# Regulators.net
KiCad netlist of a schematic drawn in Altium Designer
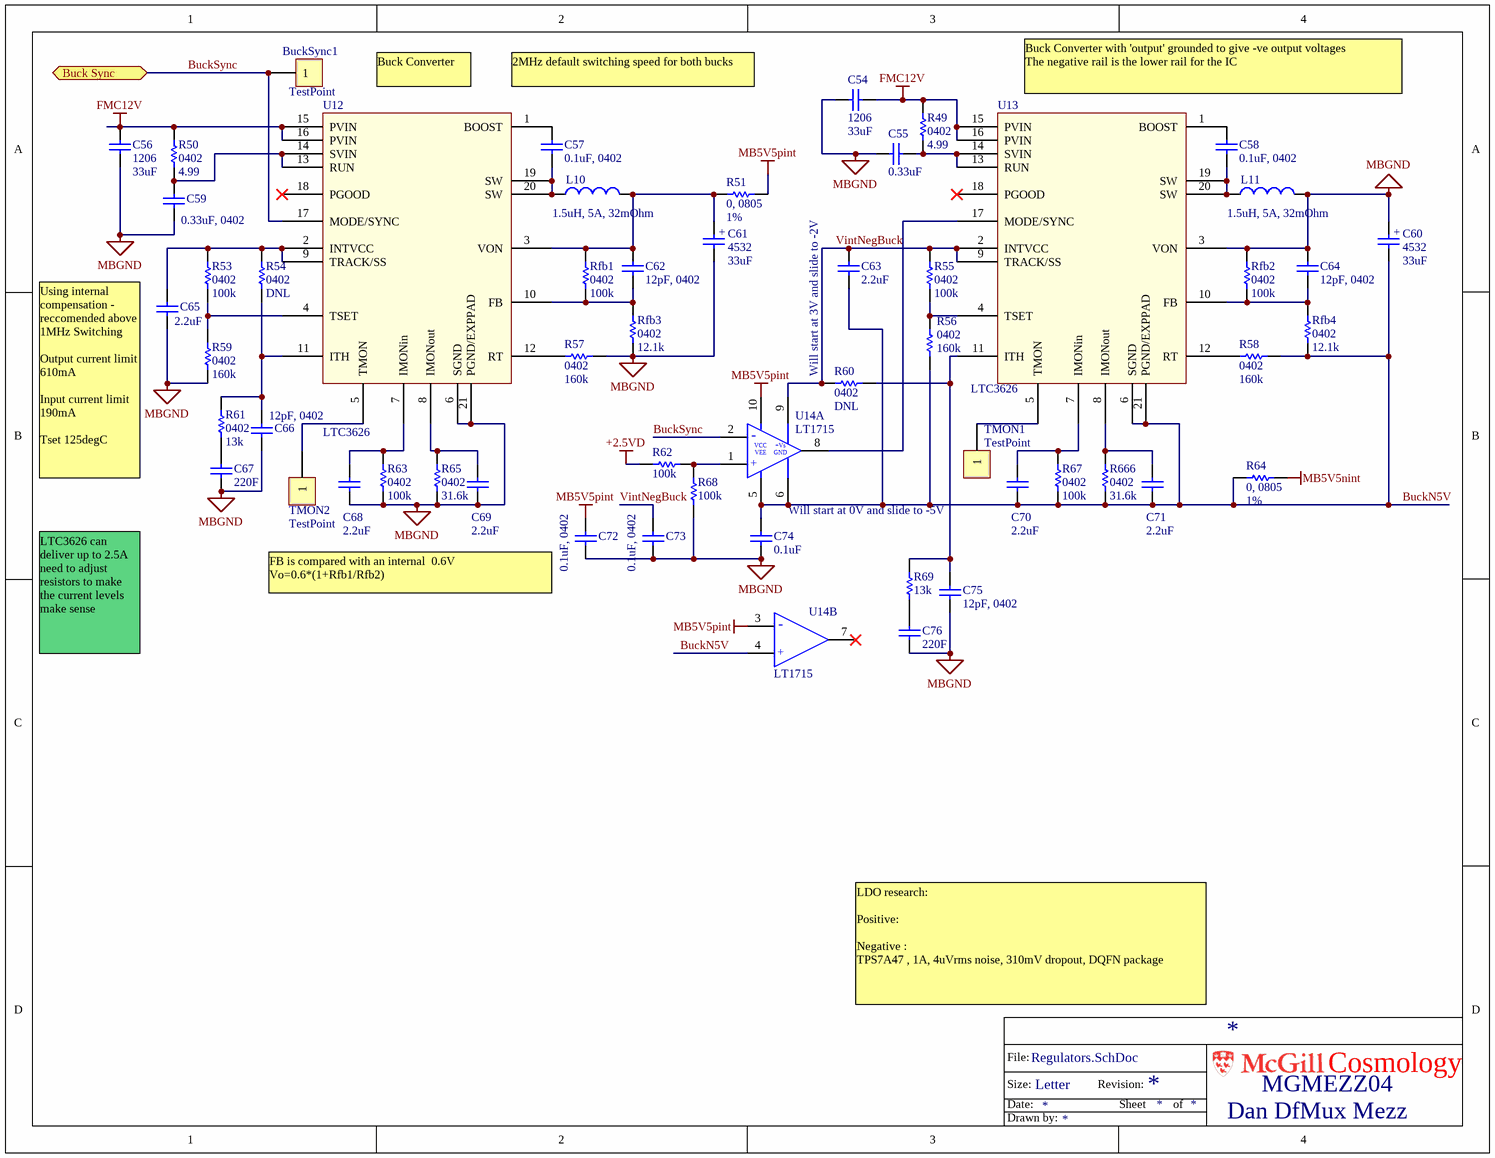
[diagram p0: Regulators.SchDoc]

(export (version "E")
  (design (tool "Eeschema 10.0.6"))
  (components
    (comp (ref "BuckSync1")
      (value "TestPoint")
      (footprint "TP-3520-SK")
      (description "TestPoint1")
      (libsource (lib "") (part "TestPoint_1"))
    )
    (comp (ref "C54")
      (value "33uF")
      (footprint "1206")
      (description "Capacitor, Ceramic, 1210")
      (fields
        (field (name "MANUFACTURER") "TDK Corporation")
        (field (name "MANUFACTURERS PART NUMBER") "C3216X5R1E336M")
      )
      (libsource (lib "MGMEZZ04") (part "CAP 1210"))
    )
    (comp (ref "C55")
      (value "0.33uF")
      (footprint "0603")
      (description "Capacitor, Ceramic, 0603")
      (fields (field (name "MANUFACTURER") "Generic"))
      (libsource (lib "MGMEZZ04") (part "CAP 0603"))
    )
    (comp (ref "C56")
      (value "33uF")
      (footprint "1206")
      (description "Capacitor, Ceramic, 1210")
      (fields
        (field (name "MANUFACTURER") "TDK Corporation")
        (field (name "MANUFACTURERS PART NUMBER") "C3216X5R1E336M")
      )
      (libsource (lib "MGMEZZ04") (part "CAP 1210"))
    )
    (comp (ref "C57")
      (value "0.1uF, 0402")
      (footprint "0402")
      (description "Capacitor, Ceramic, 0402")
      (fields (field (name "MANUFACTURER") "Generic") (field (name "TOLERANCE") "±10%"))
      (libsource (lib "MGMEZZ04") (part "CAP 0603"))
    )
    (comp (ref "C58")
      (value "0.1uF, 0402")
      (footprint "0402")
      (description "Capacitor, Ceramic, 0402")
      (fields (field (name "MANUFACTURER") "Generic") (field (name "TOLERANCE") "±10%"))
      (libsource (lib "MGMEZZ04") (part "CAP 0603"))
    )
    (comp (ref "C59")
      (value "0.33uF, 0402")
      (footprint "0402")
      (description "Capacitor, Ceramic, 0402")
      (fields (field (name "MANUFACTURER") "Generic") (field (name "TOLERANCE") "±10%"))
      (libsource (lib "MGMEZZ04") (part "CAP 0603"))
    )
    (comp (ref "C60")
      (value "33uF")
      (footprint "4532")
      (description "33u, 16V, 20%, 4532C, X5R")
      (fields
        (field (name "MANUFACTURER") "TDK Corporation")
        (field (name "MANUFACTURERS PART NUMBER") "C4532X5R1C336M")
      )
      (libsource (lib "MGMEZZ04") (part "CAP4532"))
    )
    (comp (ref "C61")
      (value "33uF")
      (footprint "4532")
      (description "33u, 16V, 20%, 4532C, X5R")
      (fields
        (field (name "MANUFACTURER") "TDK Corporation")
        (field (name "MANUFACTURERS PART NUMBER") "C4532X5R1C336M")
      )
      (libsource (lib "MGMEZZ04") (part "CAP4532"))
    )
    (comp (ref "C62")
      (value "12pF, 0402")
      (footprint "0402")
      (description "Capacitor, Ceramic, 0603")
      (fields (field (name "MANUFACTURER") "Generic"))
      (libsource (lib "MGMEZZ04") (part "CAP 0402"))
    )
    (comp (ref "C63")
      (value "2.2uF")
      (footprint "0603")
      (description "Capacitor, Ceramic, 0603")
      (fields (field (name "MANUFACTURER") "Generic"))
      (libsource (lib "MGMEZZ04") (part "CAP 0603"))
    )
    (comp (ref "C64")
      (value "12pF, 0402")
      (footprint "0402")
      (description "Capacitor, Ceramic, 0603")
      (fields (field (name "MANUFACTURER") "Generic"))
      (libsource (lib "MGMEZZ04") (part "CAP 0402"))
    )
    (comp (ref "C65")
      (value "2.2uF")
      (footprint "0603")
      (description "Capacitor, Ceramic, 0603")
      (fields (field (name "MANUFACTURER") "Generic"))
      (libsource (lib "MGMEZZ04") (part "CAP 0603"))
    )
    (comp (ref "C66")
      (value "12pF, 0402")
      (footprint "0402")
      (description "Capacitor, Ceramic, 0603")
      (fields (field (name "MANUFACTURER") "Generic"))
      (libsource (lib "MGMEZZ04") (part "CAP 0402"))
    )
    (comp (ref "C67")
      (value "220F")
      (footprint "0603")
      (description "Capacitor, Ceramic, 0603")
      (fields (field (name "MANUFACTURER") "Generic"))
      (libsource (lib "MGMEZZ04") (part "CAP 0603"))
    )
    (comp (ref "C68")
      (value "2.2uF")
      (footprint "0603")
      (description "Capacitor, Ceramic, 0603")
      (fields (field (name "MANUFACTURER") "Generic") (field (name "TOLERANCE") "±10%"))
      (libsource (lib "MGMEZZ04") (part "CAP 0603"))
    )
    (comp (ref "C69")
      (value "2.2uF")
      (footprint "0603")
      (description "Capacitor, Ceramic, 0603")
      (fields (field (name "MANUFACTURER") "Generic") (field (name "TOLERANCE") "±10%"))
      (libsource (lib "MGMEZZ04") (part "CAP 0603"))
    )
    (comp (ref "C70")
      (value "2.2uF")
      (footprint "0603")
      (description "Capacitor, Ceramic, 0603")
      (fields (field (name "MANUFACTURER") "Generic") (field (name "TOLERANCE") "±10%"))
      (libsource (lib "MGMEZZ04") (part "CAP 0603"))
    )
    (comp (ref "C71")
      (value "2.2uF")
      (footprint "0603")
      (description "Capacitor, Ceramic, 0603")
      (fields (field (name "MANUFACTURER") "Generic") (field (name "TOLERANCE") "±10%"))
      (libsource (lib "MGMEZZ04") (part "CAP 0603"))
    )
    (comp (ref "C72")
      (value "0.1uF, 0402")
      (footprint "0402")
      (description "Capacitor, Ceramic, 0402")
      (fields (field (name "MANUFACTURER") "Generic") (field (name "TOLERANCE") "±10%"))
      (libsource (lib "MGMEZZ04") (part "CAP 0603"))
    )
    (comp (ref "C73")
      (value "0.1uF, 0402")
      (footprint "0402")
      (description "Capacitor, Ceramic, 0402")
      (fields (field (name "MANUFACTURER") "Generic") (field (name "TOLERANCE") "±10%"))
      (libsource (lib "MGMEZZ04") (part "CAP 0603"))
    )
    (comp (ref "C74")
      (value "0.1uF")
      (footprint "0603")
      (description "Capacitor, Ceramic, 0603")
      (fields (field (name "MANUFACTURER") "Generic"))
      (libsource (lib "MGMEZZ04") (part "CAP 0603"))
    )
    (comp (ref "C75")
      (value "12pF, 0402")
      (footprint "0402")
      (description "Capacitor, Ceramic, 0603")
      (fields (field (name "MANUFACTURER") "Generic"))
      (libsource (lib "MGMEZZ04") (part "CAP 0402"))
    )
    (comp (ref "C76")
      (value "220F")
      (footprint "0603")
      (description "Capacitor, Ceramic, 0603")
      (fields (field (name "MANUFACTURER") "Generic"))
      (libsource (lib "MGMEZZ04") (part "CAP 0603"))
    )
    (comp (ref "L10")
      (value "1.5uH")
      (footprint "IHLP-1212")
      (description "Inductor IHLP1212")
      (fields
        (field (name "MANUFACTURER") "Vishay Dale")
        (field (name "MANUFACTURERS PART NUMBER") "IHLP1212BZER1R5M11")
        (field (name "PART CONSTRAINTS") "1.5uH, 5A, 32mOhm")
      )
      (libsource (lib "MGMEZZ04") (part "IND IHLP1212"))
    )
    (comp (ref "L11")
      (value "1.5uH")
      (footprint "IHLP-1212")
      (description "Inductor IHLP1212")
      (fields
        (field (name "MANUFACTURER") "Vishay Dale")
        (field (name "MANUFACTURERS PART NUMBER") "IHLP1212BZER1R5M11")
        (field (name "PART CONSTRAINTS") "1.5uH, 5A, 32mOhm")
      )
      (libsource (lib "MGMEZZ04") (part "IND IHLP1212"))
    )
    (comp (ref "R49")
      (value "4.99")
      (footprint "0402")
      (description "Resistor")
      (fields (field (name "MANUFACTURER") "Generic"))
      (libsource (lib "MGMEZZ04") (part "RES 0402"))
    )
    (comp (ref "R50")
      (value "4.99")
      (footprint "0402")
      (description "Resistor")
      (fields (field (name "MANUFACTURER") "Generic"))
      (libsource (lib "MGMEZZ04") (part "RES 0402"))
    )
    (comp (ref "R51")
      (value "0, 0805")
      (footprint "0805")
      (description "RES 0.0 OHM 1/8W 0805 SMD")
      (fields (field (name "PARAM") "1%") (field (name "MANUFACTURER") "e.g Vishay/Dale"))
      (libsource (lib "AdamsParts") (part "Res1812"))
    )
    (comp (ref "R53")
      (value "100k")
      (footprint "0402")
      (description "Resistor")
      (fields (field (name "MANUFACTURER") "Generic"))
      (libsource (lib "MGMEZZ04") (part "RES 0402"))
    )
    (comp (ref "R54")
      (value "DNL")
      (footprint "0402")
      (description "Resistor")
      (fields (field (name "MANUFACTURER") "Generic"))
      (libsource (lib "MGMEZZ04") (part "RES 0402"))
    )
    (comp (ref "R55")
      (value "100k")
      (footprint "0402")
      (description "Resistor")
      (fields (field (name "MANUFACTURER") "Generic"))
      (libsource (lib "MGMEZZ04") (part "RES 0402"))
    )
    (comp (ref "R56")
      (value "160k")
      (footprint "0402")
      (description "Resistor")
      (fields (field (name "MANUFACTURER") "Generic"))
      (libsource (lib "MGMEZZ04") (part "RES 0402"))
    )
    (comp (ref "R57")
      (value "160k")
      (footprint "0402")
      (description "Resistor")
      (fields (field (name "MANUFACTURER") "Generic"))
      (libsource (lib "MGMEZZ04") (part "RES 0402"))
    )
    (comp (ref "R58")
      (value "160k")
      (footprint "0402")
      (description "Resistor")
      (fields (field (name "MANUFACTURER") "Generic"))
      (libsource (lib "MGMEZZ04") (part "RES 0402"))
    )
    (comp (ref "R59")
      (value "160k")
      (footprint "0402")
      (description "Resistor")
      (fields (field (name "MANUFACTURER") "Generic"))
      (libsource (lib "MGMEZZ04") (part "RES 0402"))
    )
    (comp (ref "R60")
      (value "DNL")
      (footprint "0402")
      (description "Resistor")
      (fields (field (name "MANUFACTURER") "Generic"))
      (libsource (lib "MGMEZZ04") (part "RES 0402"))
    )
    (comp (ref "R61")
      (value "13k")
      (footprint "0402")
      (description "Resistor")
      (fields (field (name "MANUFACTURER") "Generic"))
      (libsource (lib "MGMEZZ04") (part "RES 0402"))
    )
    (comp (ref "R62")
      (value "100k")
      (footprint "0603")
      (description "Resistor")
      (fields (field (name "MANUFACTURER") "Generic"))
      (libsource (lib "MGMEZZ04") (part "RES 0603"))
    )
    (comp (ref "R63")
      (value "100k")
      (footprint "0402")
      (description "Resistor")
      (fields (field (name "MANUFACTURER") "Generic"))
      (libsource (lib "MGMEZZ04") (part "RES 0402"))
    )
    (comp (ref "R64")
      (value "0, 0805")
      (footprint "0805")
      (description "RES 0.0 OHM 1/8W 0805 SMD")
      (fields (field (name "PARAM") "1%") (field (name "MANUFACTURER") "e.g Vishay/Dale"))
      (libsource (lib "AdamsParts") (part "Res1812"))
    )
    (comp (ref "R65")
      (value "31.6k")
      (footprint "0402")
      (description "Resistor")
      (fields (field (name "MANUFACTURER") "Generic"))
      (libsource (lib "MGMEZZ04") (part "RES 0402"))
    )
    (comp (ref "R67")
      (value "100k")
      (footprint "0402")
      (description "Resistor")
      (fields (field (name "MANUFACTURER") "Generic"))
      (libsource (lib "MGMEZZ04") (part "RES 0402"))
    )
    (comp (ref "R68")
      (value "100k")
      (footprint "0603")
      (description "Resistor")
      (fields (field (name "MANUFACTURER") "Generic"))
      (libsource (lib "MGMEZZ04") (part "RES 0603"))
    )
    (comp (ref "R69")
      (value "13k")
      (footprint "0603")
      (description "Resistor")
      (fields (field (name "MANUFACTURER") "Generic"))
      (libsource (lib "MGMEZZ04") (part "RES 0603"))
    )
    (comp (ref "R666")
      (value "31.6k")
      (footprint "0402")
      (description "Resistor")
      (fields (field (name "MANUFACTURER") "Generic"))
      (libsource (lib "MGMEZZ04") (part "RES 0402"))
    )
    (comp (ref "Rfb1")
      (value "100k")
      (footprint "0402")
      (description "Resistor")
      (fields (field (name "MANUFACTURER") "Generic"))
      (libsource (lib "MGMEZZ04") (part "RES 0402"))
    )
    (comp (ref "Rfb2")
      (value "100k")
      (footprint "0402")
      (description "Resistor")
      (fields (field (name "MANUFACTURER") "Generic"))
      (libsource (lib "MGMEZZ04") (part "RES 0402"))
    )
    (comp (ref "Rfb3")
      (value "12.1k")
      (footprint "0402")
      (description "Resistor")
      (fields (field (name "MANUFACTURER") "Generic"))
      (libsource (lib "MGMEZZ04") (part "RES 0402"))
    )
    (comp (ref "Rfb4")
      (value "12.1k")
      (footprint "0402")
      (description "Resistor")
      (fields (field (name "MANUFACTURER") "Generic"))
      (libsource (lib "MGMEZZ04") (part "RES 0402"))
    )
    (comp (ref "TMON1")
      (value "TestPoint")
      (footprint "TP-3520-SK")
      (description "TestPoint1")
      (libsource (lib "MGMEZZ04") (part "TestPoint"))
    )
    (comp (ref "TMON2")
      (value "TestPoint")
      (footprint "TP-3520-SK")
      (description "TestPoint1")
      (libsource (lib "MGMEZZ04") (part "TestPoint"))
    )
    (comp (ref "U12")
      (value "LTC3626")
      (footprint "LTC3626")
      (description "20V, 2.5A Sync buck, 3Mhz")
      (fields
        (field (name "MANUFACTURERS PART NUMBER") "LTC3626EUDC#PBF")
        (field (name "MANUFACTURER") "Linear Technology")
      )
      (libsource (lib "MGMEZZ04") (part "LTC3626"))
    )
    (comp (ref "U13")
      (value "LTC3626")
      (footprint "LTC3626")
      (description "20V, 2.5A Sync buck, 3Mhz")
      (fields
        (field (name "MANUFACTURERS PART NUMBER") "LTC3626EUDC#PBF")
        (field (name "MANUFACTURER") "Linear Technology")
      )
      (libsource (lib "MGMEZZ04") (part "LTC3626"))
    )
    (comp (ref "U14")
      (value "LT1715")
      (footprint "TSSOP50P490X110-10N")
      (description "Comparator with two supplies")
      (libsource (lib "MGMEZZ04") (part "LT1715"))
    )
  )
  (nets
    (net (code "1") (name "+2.5VD") (class "Default")
      (node (ref "R62") (pin "2") (pinfunction "2_2") (pintype "passive"))
    )
    (net (code "2") (name "/BuckN5V") (class "Default")
      (node (ref "C60") (pin "2") (pinfunction "2_2") (pintype "passive"))
      (node (ref "C63") (pin "1") (pinfunction "1_1") (pintype "passive"))
      (node (ref "C70") (pin "2") (pinfunction "2_2") (pintype "passive"))
      (node (ref "C71") (pin "2") (pinfunction "2_2") (pintype "passive"))
      (node (ref "C74") (pin "2") (pinfunction "2_2") (pintype "passive"))
      (node (ref "R56") (pin "2") (pinfunction "2_2") (pintype "passive"))
      (node (ref "R58") (pin "2") (pinfunction "2_2") (pintype "passive"))
      (node (ref "R64") (pin "2") (pinfunction "2_2") (pintype "passive"))
      (node (ref "R666") (pin "2") (pinfunction "2_2") (pintype "passive"))
      (node (ref "R67") (pin "2") (pinfunction "2_2") (pintype "passive"))
      (node (ref "Rfb4") (pin "2") (pinfunction "2_2") (pintype "passive"))
      (node (ref "U13") (pin "21") (pinfunction "PGND/EXPPAD_21") (pintype "passive"))
      (node (ref "U13") (pin "6") (pinfunction "SGND_6") (pintype "passive"))
      (node (ref "U14") (pin "4") (pinfunction "+_4") (pintype "passive"))
      (node (ref "U14") (pin "5") (pinfunction "Vee_5") (pintype "power_in"))
      (node (ref "U14") (pin "6") (pinfunction "Gnd_6") (pintype "power_in"))
    )
    (net (code "3") (name "/BuckSync") (class "Default")
      (node (ref "BuckSync1") (pin "1") (pinfunction "1_1") (pintype "passive"))
      (node (ref "U12") (pin "17") (pinfunction "MODE/SYNC_17") (pintype "passive"))
      (node (ref "U14") (pin "2") (pinfunction "-_2") (pintype "power_in"))
    )
    (net (code "4") (name "/VintNegBuck") (class "Default")
      (node (ref "C63") (pin "2") (pinfunction "2_2") (pintype "passive"))
      (node (ref "C73") (pin "2") (pinfunction "2_2") (pintype "passive"))
      (node (ref "R55") (pin "1") (pinfunction "1_1") (pintype "passive"))
      (node (ref "R60") (pin "1") (pinfunction "1_1") (pintype "passive"))
      (node (ref "U13") (pin "2") (pinfunction "INTVCC_2") (pintype "passive"))
      (node (ref "U13") (pin "9") (pinfunction "TRACK/SS_9") (pintype "passive"))
      (node (ref "U14") (pin "9") (pinfunction "Vs_9") (pintype "power_in"))
    )
    (net (code "5") (name "FMC12V") (class "Default")
      (node (ref "C54") (pin "1") (pinfunction "1_1") (pintype "passive"))
      (node (ref "C56") (pin "1") (pinfunction "1_1") (pintype "passive"))
      (node (ref "R49") (pin "1") (pinfunction "1_1") (pintype "passive"))
      (node (ref "R50") (pin "1") (pinfunction "1_1") (pintype "passive"))
      (node (ref "U12") (pin "15") (pinfunction "PVIN_15") (pintype "passive"))
      (node (ref "U12") (pin "16") (pinfunction "PVIN_16") (pintype "passive"))
      (node (ref "U13") (pin "15") (pinfunction "PVIN_15") (pintype "passive"))
      (node (ref "U13") (pin "16") (pinfunction "PVIN_16") (pintype "passive"))
    )
    (net (code "6") (name "MB5V5nint") (class "Default")
      (node (ref "R64") (pin "1") (pinfunction "1_1") (pintype "passive"))
    )
    (net (code "7") (name "MB5V5pint") (class "Default")
      (node (ref "C72") (pin "2") (pinfunction "2_2") (pintype "passive"))
      (node (ref "R51") (pin "1") (pinfunction "1_1") (pintype "passive"))
      (node (ref "U14") (pin "10") (pinfunction "Vcc_10") (pintype "power_in"))
      (node (ref "U14") (pin "3") (pinfunction "-_3") (pintype "power_in"))
    )
    (net (code "8") (name "MBGND") (class "Default")
      (node (ref "C54") (pin "2") (pinfunction "2_2") (pintype "passive"))
      (node (ref "C55") (pin "1") (pinfunction "1_1") (pintype "passive"))
      (node (ref "C56") (pin "2") (pinfunction "2_2") (pintype "passive"))
      (node (ref "C59") (pin "1") (pinfunction "1_1") (pintype "passive"))
      (node (ref "C60") (pin "1") (pinfunction "1_1") (pintype "passive"))
      (node (ref "C61") (pin "2") (pinfunction "2_2") (pintype "passive"))
      (node (ref "C64") (pin "2") (pinfunction "2_2") (pintype "passive"))
      (node (ref "C65") (pin "1") (pinfunction "1_1") (pintype "passive"))
      (node (ref "C66") (pin "1") (pinfunction "1_1") (pintype "passive"))
      (node (ref "C67") (pin "2") (pinfunction "2_2") (pintype "passive"))
      (node (ref "C68") (pin "2") (pinfunction "2_2") (pintype "passive"))
      (node (ref "C69") (pin "2") (pinfunction "2_2") (pintype "passive"))
      (node (ref "C72") (pin "1") (pinfunction "1_1") (pintype "passive"))
      (node (ref "C73") (pin "1") (pinfunction "1_1") (pintype "passive"))
      (node (ref "C74") (pin "1") (pinfunction "1_1") (pintype "passive"))
      (node (ref "C75") (pin "1") (pinfunction "1_1") (pintype "passive"))
      (node (ref "C76") (pin "2") (pinfunction "2_2") (pintype "passive"))
      (node (ref "L11") (pin "2") (pinfunction "2_2") (pintype "passive"))
      (node (ref "R57") (pin "2") (pinfunction "2_2") (pintype "passive"))
      (node (ref "R59") (pin "2") (pinfunction "2_2") (pintype "passive"))
      (node (ref "R63") (pin "2") (pinfunction "2_2") (pintype "passive"))
      (node (ref "R65") (pin "2") (pinfunction "2_2") (pintype "passive"))
      (node (ref "R68") (pin "2") (pinfunction "2_2") (pintype "passive"))
      (node (ref "Rfb2") (pin "1") (pinfunction "1_1") (pintype "passive"))
      (node (ref "Rfb3") (pin "2") (pinfunction "2_2") (pintype "passive"))
      (node (ref "U12") (pin "21") (pinfunction "PGND/EXPPAD_21") (pintype "passive"))
      (node (ref "U12") (pin "6") (pinfunction "SGND_6") (pintype "passive"))
      (node (ref "U13") (pin "3") (pinfunction "VON_3") (pintype "passive"))
    )
    (net (code "9") (name "Net-(C57-Pad1)") (class "Default")
      (node (ref "C57") (pin "1") (pinfunction "1_1") (pintype "passive"))
      (node (ref "L10") (pin "1") (pinfunction "1_1") (pintype "passive"))
      (node (ref "U12") (pin "19") (pinfunction "SW_19") (pintype "passive"))
      (node (ref "U12") (pin "20") (pinfunction "SW_20") (pintype "passive"))
    )
    (net (code "10") (name "Net-(C58-Pad1)") (class "Default")
      (node (ref "C58") (pin "1") (pinfunction "1_1") (pintype "passive"))
      (node (ref "L11") (pin "1") (pinfunction "1_1") (pintype "passive"))
      (node (ref "U13") (pin "19") (pinfunction "SW_19") (pintype "passive"))
      (node (ref "U13") (pin "20") (pinfunction "SW_20") (pintype "passive"))
    )
    (net (code "11") (name "Net-(C67-Pad1)") (class "Default")
      (node (ref "C67") (pin "1") (pinfunction "1_1") (pintype "passive"))
      (node (ref "R61") (pin "2") (pinfunction "2_2") (pintype "passive"))
    )
    (net (code "12") (name "Net-(C76-Pad1)") (class "Default")
      (node (ref "C76") (pin "1") (pinfunction "1_1") (pintype "passive"))
      (node (ref "R69") (pin "1") (pinfunction "1_1") (pintype "passive"))
    )
    (net (code "13") (name "Net-(U12-BOOST)") (class "Default")
      (node (ref "C57") (pin "2") (pinfunction "2_2") (pintype "passive"))
      (node (ref "U12") (pin "1") (pinfunction "BOOST_1") (pintype "passive"))
    )
    (net (code "14") (name "Net-(U12-FB)") (class "Default")
      (node (ref "C62") (pin "1") (pinfunction "1_1") (pintype "passive"))
      (node (ref "Rfb1") (pin "2") (pinfunction "2_2") (pintype "passive"))
      (node (ref "Rfb3") (pin "1") (pinfunction "1_1") (pintype "passive"))
      (node (ref "U12") (pin "10") (pinfunction "FB_10") (pintype "passive"))
    )
    (net (code "15") (name "Net-(U12-IMONin)") (class "Default")
      (node (ref "C68") (pin "1") (pinfunction "1_1") (pintype "passive"))
      (node (ref "R63") (pin "1") (pinfunction "1_1") (pintype "passive"))
      (node (ref "U12") (pin "7") (pinfunction "IMONin_7") (pintype "passive"))
    )
    (net (code "16") (name "Net-(U12-IMONout)") (class "Default")
      (node (ref "C69") (pin "1") (pinfunction "1_1") (pintype "passive"))
      (node (ref "R65") (pin "1") (pinfunction "1_1") (pintype "passive"))
      (node (ref "U12") (pin "8") (pinfunction "IMONout_8") (pintype "passive"))
    )
    (net (code "17") (name "Net-(U12-INTVCC)") (class "Default")
      (node (ref "C65") (pin "2") (pinfunction "2_2") (pintype "passive"))
      (node (ref "R53") (pin "1") (pinfunction "1_1") (pintype "passive"))
      (node (ref "R54") (pin "1") (pinfunction "1_1") (pintype "passive"))
      (node (ref "U12") (pin "2") (pinfunction "INTVCC_2") (pintype "passive"))
      (node (ref "U12") (pin "9") (pinfunction "TRACK/SS_9") (pintype "passive"))
    )
    (net (code "18") (name "Net-(U12-ITH)") (class "Default")
      (node (ref "C66") (pin "2") (pinfunction "2_2") (pintype "passive"))
      (node (ref "R54") (pin "2") (pinfunction "2_2") (pintype "passive"))
      (node (ref "R61") (pin "1") (pinfunction "1_1") (pintype "passive"))
      (node (ref "U12") (pin "11") (pinfunction "ITH_11") (pintype "passive"))
    )
    (net (code "19") (name "Net-(U12-RT)") (class "Default")
      (node (ref "R57") (pin "1") (pinfunction "1_1") (pintype "passive"))
      (node (ref "U12") (pin "12") (pinfunction "RT_12") (pintype "passive"))
    )
    (net (code "20") (name "Net-(U12-RUN)") (class "Default")
      (node (ref "C59") (pin "2") (pinfunction "2_2") (pintype "passive"))
      (node (ref "R50") (pin "2") (pinfunction "2_2") (pintype "passive"))
      (node (ref "U12") (pin "13") (pinfunction "RUN_13") (pintype "passive"))
      (node (ref "U12") (pin "14") (pinfunction "SVIN_14") (pintype "passive"))
    )
    (net (code "21") (name "Net-(U12-TMON)") (class "Default")
      (node (ref "TMON2") (pin "1") (pinfunction "1_1") (pintype "passive"))
      (node (ref "U12") (pin "5") (pinfunction "TMON_5") (pintype "passive"))
    )
    (net (code "22") (name "Net-(U12-TSET)") (class "Default")
      (node (ref "R53") (pin "2") (pinfunction "2_2") (pintype "passive"))
      (node (ref "R59") (pin "1") (pinfunction "1_1") (pintype "passive"))
      (node (ref "U12") (pin "4") (pinfunction "TSET_4") (pintype "passive"))
    )
    (net (code "23") (name "Net-(U12-VON)") (class "Default")
      (node (ref "C61") (pin "1") (pinfunction "1_1") (pintype "passive"))
      (node (ref "C62") (pin "2") (pinfunction "2_2") (pintype "passive"))
      (node (ref "L10") (pin "2") (pinfunction "2_2") (pintype "passive"))
      (node (ref "R51") (pin "2") (pinfunction "2_2") (pintype "passive"))
      (node (ref "Rfb1") (pin "1") (pinfunction "1_1") (pintype "passive"))
      (node (ref "U12") (pin "3") (pinfunction "VON_3") (pintype "passive"))
    )
    (net (code "24") (name "Net-(U13-BOOST)") (class "Default")
      (node (ref "C58") (pin "2") (pinfunction "2_2") (pintype "passive"))
      (node (ref "U13") (pin "1") (pinfunction "BOOST_1") (pintype "passive"))
    )
    (net (code "25") (name "Net-(U13-FB)") (class "Default")
      (node (ref "C64") (pin "1") (pinfunction "1_1") (pintype "passive"))
      (node (ref "Rfb2") (pin "2") (pinfunction "2_2") (pintype "passive"))
      (node (ref "Rfb4") (pin "1") (pinfunction "1_1") (pintype "passive"))
      (node (ref "U13") (pin "10") (pinfunction "FB_10") (pintype "passive"))
    )
    (net (code "26") (name "Net-(U13-IMONin)") (class "Default")
      (node (ref "C70") (pin "1") (pinfunction "1_1") (pintype "passive"))
      (node (ref "R67") (pin "1") (pinfunction "1_1") (pintype "passive"))
      (node (ref "U13") (pin "7") (pinfunction "IMONin_7") (pintype "passive"))
    )
    (net (code "27") (name "Net-(U13-IMONout)") (class "Default")
      (node (ref "C71") (pin "1") (pinfunction "1_1") (pintype "passive"))
      (node (ref "R666") (pin "1") (pinfunction "1_1") (pintype "passive"))
      (node (ref "U13") (pin "8") (pinfunction "IMONout_8") (pintype "passive"))
    )
    (net (code "28") (name "Net-(U13-ITH)") (class "Default")
      (node (ref "C75") (pin "2") (pinfunction "2_2") (pintype "passive"))
      (node (ref "R60") (pin "2") (pinfunction "2_2") (pintype "passive"))
      (node (ref "R69") (pin "2") (pinfunction "2_2") (pintype "passive"))
      (node (ref "U13") (pin "11") (pinfunction "ITH_11") (pintype "passive"))
    )
    (net (code "29") (name "Net-(U13-MODE{slash}SYNC)") (class "Default")
      (node (ref "U13") (pin "17") (pinfunction "MODE/SYNC_17") (pintype "passive"))
      (node (ref "U14") (pin "8") (pinfunction "Out_8") (pintype "passive"))
    )
    (net (code "30") (name "Net-(U13-RT)") (class "Default")
      (node (ref "R58") (pin "1") (pinfunction "1_1") (pintype "passive"))
      (node (ref "U13") (pin "12") (pinfunction "RT_12") (pintype "passive"))
    )
    (net (code "31") (name "Net-(U13-RUN)") (class "Default")
      (node (ref "C55") (pin "2") (pinfunction "2_2") (pintype "passive"))
      (node (ref "R49") (pin "2") (pinfunction "2_2") (pintype "passive"))
      (node (ref "U13") (pin "13") (pinfunction "RUN_13") (pintype "passive"))
      (node (ref "U13") (pin "14") (pinfunction "SVIN_14") (pintype "passive"))
    )
    (net (code "32") (name "Net-(U13-TMON)") (class "Default")
      (node (ref "TMON1") (pin "1") (pinfunction "1_1") (pintype "passive"))
      (node (ref "U13") (pin "5") (pinfunction "TMON_5") (pintype "passive"))
    )
    (net (code "33") (name "Net-(U13-TSET)") (class "Default")
      (node (ref "R55") (pin "2") (pinfunction "2_2") (pintype "passive"))
      (node (ref "R56") (pin "1") (pinfunction "1_1") (pintype "passive"))
      (node (ref "U13") (pin "4") (pinfunction "TSET_4") (pintype "passive"))
    )
    (net (code "34") (name "Net-(U14A-+)") (class "Default")
      (node (ref "R62") (pin "1") (pinfunction "1_1") (pintype "passive"))
      (node (ref "R68") (pin "1") (pinfunction "1_1") (pintype "passive"))
      (node (ref "U14") (pin "1") (pinfunction "+_1") (pintype "passive"))
    )
    (net (code "35") (name "unconnected-(U12-PGOOD-Pad18)") (class "Default")
      (node (ref "U12") (pin "18") (pinfunction "PGOOD_18") (pintype "passive+no_connect"))
    )
    (net (code "36") (name "unconnected-(U13-PGOOD-Pad18)") (class "Default")
      (node (ref "U13") (pin "18") (pinfunction "PGOOD_18") (pintype "passive+no_connect"))
    )
    (net (code "37") (name "unconnected-(U14B-Out-Pad7)") (class "Default")
      (node (ref "U14") (pin "7") (pinfunction "Out_7") (pintype "passive+no_connect"))
    )
  )
)
